# main.net
KiCad netlist of a schematic drawn in Altium Designer
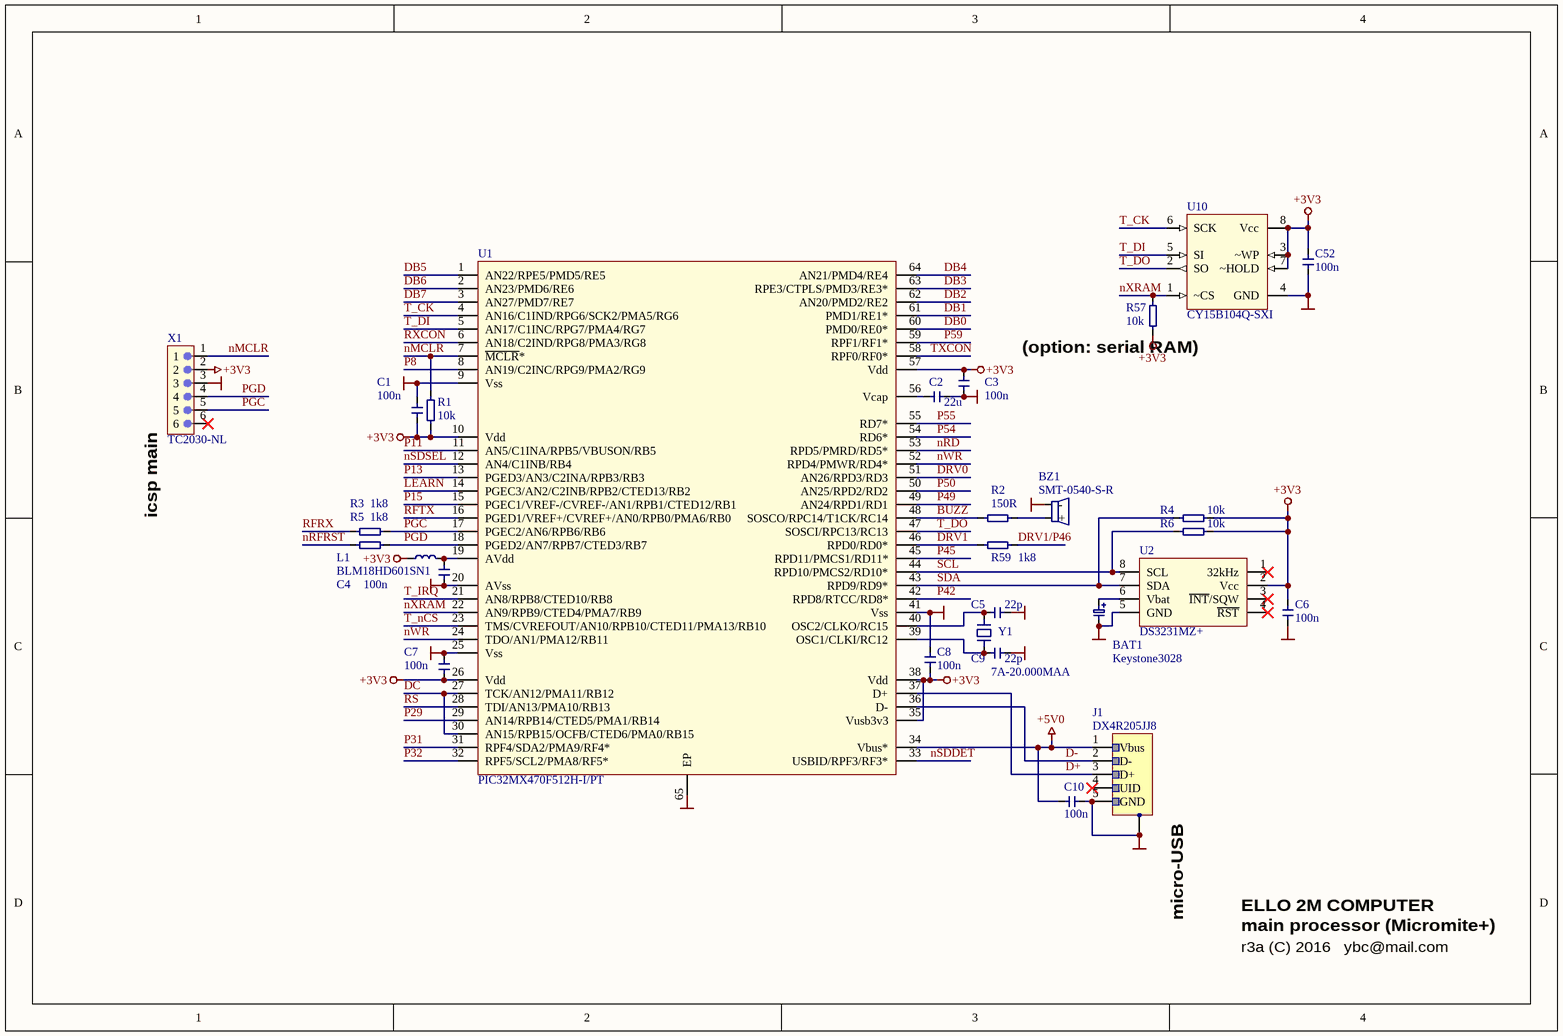
[diagram p0: main.SchDoc]

(export (version "E")
  (design (tool "Eeschema 10.0.6"))
  (components
    (comp (ref "BAT1")
      (value "Keystone3028")
      (footprint "KEYSTONE3028/34")
      (description "Polar capacitor")
      (libsource (lib "Discretes") (part "Capacitor+"))
    )
    (comp (ref "BZ1")
      (value "SMT-0540-S-R")
      (footprint "SMT-0540-S-R")
      (description "Speaker/Buzzer")
      (libsource (lib "Discretes") (part "Speaker"))
    )
    (comp (ref "C1")
      (value "100n")
      (footprint "_0603")
      (description "Capacitor")
      (libsource (lib "Discretes") (part "Capacitor"))
    )
    (comp (ref "C2")
      (value "22u")
      (footprint "_1206")
      (description "Capacitor")
      (libsource (lib "Discretes") (part "Capacitor"))
    )
    (comp (ref "C3")
      (value "100n")
      (footprint "_0603")
      (description "Capacitor")
      (libsource (lib "Discretes") (part "Capacitor"))
    )
    (comp (ref "C4")
      (value "100n")
      (footprint "_0603")
      (description "Capacitor")
      (libsource (lib "Discretes") (part "Capacitor"))
    )
    (comp (ref "C5")
      (value "22p")
      (footprint "_0603")
      (description "Capacitor")
      (libsource (lib "Discretes") (part "Capacitor"))
    )
    (comp (ref "C6")
      (value "100n")
      (footprint "_0603")
      (description "Capacitor")
      (libsource (lib "Discretes") (part "Capacitor"))
    )
    (comp (ref "C7")
      (value "100n")
      (footprint "_0603")
      (description "Capacitor")
      (libsource (lib "Discretes") (part "Capacitor"))
    )
    (comp (ref "C8")
      (value "100n")
      (footprint "_0603")
      (description "Capacitor")
      (libsource (lib "Discretes") (part "Capacitor"))
    )
    (comp (ref "C9")
      (value "22p")
      (footprint "_0603")
      (description "Capacitor")
      (libsource (lib "Discretes") (part "Capacitor"))
    )
    (comp (ref "C10")
      (value "100n")
      (footprint "_0603")
      (description "Capacitor")
      (libsource (lib "Discretes") (part "Capacitor"))
    )
    (comp (ref "C52")
      (value "100n")
      (footprint "_0603")
      (description "Capacitor")
      (libsource (lib "Discretes") (part "Capacitor"))
    )
    (comp (ref "J1")
      (value "DX4R205JJ8")
      (footprint "DX4R205JJ8")
      (description "MicroUSB type A/B, 5 Position SMT Right Angle Receptacle")
      (libsource (lib "Connectors") (part "Mini/Micro USB"))
    )
    (comp (ref "L1")
      (value "BLM18HD601SN1")
      (footprint "_0603")
      (description "Inductor")
      (libsource (lib "Discretes") (part "Inductor"))
    )
    (comp (ref "R1")
      (value "10k")
      (footprint "_0603")
      (description "Resistor")
      (libsource (lib "Discretes") (part "Resistor"))
    )
    (comp (ref "R2")
      (value "150R")
      (footprint "_0603")
      (description "Resistor")
      (libsource (lib "Discretes") (part "Resistor"))
    )
    (comp (ref "R3")
      (value "1k8")
      (footprint "_0603")
      (description "Resistor")
      (libsource (lib "") (part "Resistor_2"))
    )
    (comp (ref "R4")
      (value "10k")
      (footprint "_0603")
      (description "Resistor")
      (libsource (lib "Discretes") (part "Resistor"))
    )
    (comp (ref "R5")
      (value "1k8")
      (footprint "_0603")
      (description "Resistor")
      (libsource (lib "") (part "Resistor_2"))
    )
    (comp (ref "R6")
      (value "10k")
      (footprint "_0603")
      (description "Resistor")
      (libsource (lib "Discretes") (part "Resistor"))
    )
    (comp (ref "R57")
      (value "10k")
      (footprint "_0603")
      (description "Resistor")
      (libsource (lib "") (part "Resistor_2"))
    )
    (comp (ref "R59")
      (value "1k8")
      (footprint "_0603")
      (description "Resistor")
      (libsource (lib "") (part "Resistor_1"))
    )
    (comp (ref "U1")
      (value "PIC32MX470F512H-I/PT")
      (footprint "QFP50P1200X1200X120-65N-S600")
      (fields (field (name "MANUFACTURER") "Microchip"))
      (libsource (lib "IC Microcontrollers and Processors") (part "PIC32MX4xx"))
    )
    (comp (ref "U2")
      (value "DS3231MZ+")
      (footprint "SOIC8")
      (description "I2C Real-Time Clock")
      (fields (field (name "MANUFACTURER") "Maxim Integrated"))
      (libsource (lib "IC Other Functions") (part "DS3231"))
    )
    (comp (ref "U10")
      (value "CY15B104Q-SXI")
      (footprint "SOIC127P790X216-8N")
      (description "Standard 8-pin SPI flash memory")
      (libsource (lib "IC Other Functions") (part "SPI Flash 8pin"))
    )
    (comp (ref "X1")
      (value "TC2030-NL")
      (footprint "TC2030-NL")
      (description "TC2030 nails connector")
      (fields (field (name "MANUFACTURER") "www.tag-connect.com"))
      (libsource (lib "Connectors") (part "TC2030"))
    )
    (comp (ref "Y1")
      (value "7A-20.000MAA")
      (footprint "Crystal 50x32 (2)")
      (description "Crystal Resonator")
      (libsource (lib "Discretes") (part "Crystal"))
    )
  )
  (nets
    (net (code "1") (name "+3V3") (class "Default")
      (node (ref "C1") (pin "2") (pintype "passive"))
      (node (ref "C3") (pin "1") (pintype "passive"))
      (node (ref "C52") (pin "2") (pintype "passive"))
      (node (ref "C6") (pin "1") (pintype "passive"))
      (node (ref "C7") (pin "2") (pintype "passive"))
      (node (ref "C8") (pin "2") (pintype "passive"))
      (node (ref "L1") (pin "1") (pintype "passive"))
      (node (ref "R1") (pin "1") (pintype "passive"))
      (node (ref "R4") (pin "2") (pintype "passive"))
      (node (ref "R57") (pin "1") (pintype "passive"))
      (node (ref "R6") (pin "2") (pintype "passive"))
      (node (ref "U1") (pin "10") (pinfunction "Vdd_10") (pintype "passive"))
      (node (ref "U1") (pin "26") (pinfunction "Vdd_26") (pintype "passive"))
      (node (ref "U1") (pin "35") (pinfunction "Vusb3v3_35") (pintype "passive"))
      (node (ref "U1") (pin "38") (pinfunction "Vdd_38") (pintype "passive"))
      (node (ref "U1") (pin "57") (pinfunction "Vdd_57") (pintype "passive"))
      (node (ref "U10") (pin "3") (pinfunction "~WP_3") (pintype "input"))
      (node (ref "U10") (pin "7") (pinfunction "~HOLD_7") (pintype "input"))
      (node (ref "U10") (pin "8") (pinfunction "Vcc_8") (pintype "power_in"))
      (node (ref "U2") (pin "2") (pinfunction "Vcc_2") (pintype "passive"))
      (node (ref "X1") (pin "2") (pinfunction "2_2") (pintype "passive"))
    )
    (net (code "2") (name "+5V0") (class "Default")
      (node (ref "C10") (pin "2") (pintype "passive"))
      (node (ref "J1") (pin "1") (pinfunction "Vbus_1") (pintype "passive"))
      (node (ref "U1") (pin "34") (pinfunction "Vbus*_34") (pintype "passive"))
    )
    (net (code "3") (name "/BUZZ") (class "Default")
      (node (ref "R2") (pin "1") (pintype "passive"))
      (node (ref "U1") (pin "48") (pinfunction "SOSCO/RPC14/T1CK/RC14_48") (pintype "passive"))
    )
    (net (code "4") (name "/D+") (class "Default")
      (node (ref "J1") (pin "3") (pinfunction "D+_3") (pintype "passive"))
      (node (ref "U1") (pin "37") (pinfunction "D+_37") (pintype "passive"))
    )
    (net (code "5") (name "/D-") (class "Default")
      (node (ref "J1") (pin "2") (pinfunction "D-_2") (pintype "passive"))
      (node (ref "U1") (pin "36") (pinfunction "D-_36") (pintype "passive"))
    )
    (net (code "6") (name "/DB0") (class "Default")
      (node (ref "U1") (pin "60") (pinfunction "PMD0/RE0*_60") (pintype "passive"))
    )
    (net (code "7") (name "/DB1") (class "Default")
      (node (ref "U1") (pin "61") (pinfunction "PMD1/RE1*_61") (pintype "passive"))
    )
    (net (code "8") (name "/DB2") (class "Default")
      (node (ref "U1") (pin "62") (pinfunction "AN20/PMD2/RE2_62") (pintype "passive"))
    )
    (net (code "9") (name "/DB3") (class "Default")
      (node (ref "U1") (pin "63") (pinfunction "RPE3/CTPLS/PMD3/RE3*_63") (pintype "passive"))
    )
    (net (code "10") (name "/DB4") (class "Default")
      (node (ref "U1") (pin "64") (pinfunction "AN21/PMD4/RE4_64") (pintype "passive"))
    )
    (net (code "11") (name "/DB5") (class "Default")
      (node (ref "U1") (pin "1") (pinfunction "AN22/RPE5/PMD5/RE5_1") (pintype "passive"))
    )
    (net (code "12") (name "/DB6") (class "Default")
      (node (ref "U1") (pin "2") (pinfunction "AN23/PMD6/RE6_2") (pintype "passive"))
    )
    (net (code "13") (name "/DB7") (class "Default")
      (node (ref "U1") (pin "3") (pinfunction "AN27/PMD7/RE7_3") (pintype "passive"))
    )
    (net (code "14") (name "/DC") (class "Default")
      (node (ref "U1") (pin "27") (pinfunction "TCK/AN12/PMA11/RB12_27") (pintype "passive"))
      (node (ref "U1") (pin "30") (pinfunction "AN15/RPB15/OCFB/CTED6/PMA0/RB15_30") (pintype "passive"))
    )
    (net (code "15") (name "/DRV0") (class "Default")
      (node (ref "U1") (pin "51") (pinfunction "AN26/RPD3/RD3_51") (pintype "passive"))
    )
    (net (code "16") (name "/DRV1") (class "Default")
      (node (ref "R59") (pin "2") (pintype "passive"))
      (node (ref "U1") (pin "46") (pinfunction "RPD0/RD0*_46") (pintype "passive"))
    )
    (net (code "17") (name "/DRV1{slash}P46") (class "Default")
      (node (ref "R59") (pin "1") (pintype "passive"))
    )
    (net (code "18") (name "/LEARN") (class "Default")
      (node (ref "U1") (pin "14") (pinfunction "PGEC3/AN2/C2INB/RPB2/CTED13/RB2_14") (pintype "passive"))
    )
    (net (code "19") (name "/P8") (class "Default")
      (node (ref "U1") (pin "8") (pinfunction "AN19/C2INC/RPG9/PMA2/RG9_8") (pintype "passive"))
    )
    (net (code "20") (name "/P11") (class "Default")
      (node (ref "U1") (pin "11") (pinfunction "AN5/C1INA/RPB5/VBUSON/RB5_11") (pintype "passive"))
    )
    (net (code "21") (name "/P13") (class "Default")
      (node (ref "U1") (pin "13") (pinfunction "PGED3/AN3/C2INA/RPB3/RB3_13") (pintype "passive"))
    )
    (net (code "22") (name "/P15") (class "Default")
      (node (ref "U1") (pin "15") (pinfunction "PGEC1/VREF-/CVREF-/AN1/RPB1/CTED12/RB1_15") (pintype "passive"))
    )
    (net (code "23") (name "/P29") (class "Default")
      (node (ref "U1") (pin "29") (pinfunction "AN14/RPB14/CTED5/PMA1/RB14_29") (pintype "passive"))
    )
    (net (code "24") (name "/P31") (class "Default")
      (node (ref "U1") (pin "31") (pinfunction "RPF4/SDA2/PMA9/RF4*_31") (pintype "passive"))
    )
    (net (code "25") (name "/P32") (class "Default")
      (node (ref "U1") (pin "32") (pinfunction "RPF5/SCL2/PMA8/RF5*_32") (pintype "passive"))
    )
    (net (code "26") (name "/P42") (class "Default")
      (node (ref "U1") (pin "42") (pinfunction "RPD8/RTCC/RD8*_42") (pintype "passive"))
    )
    (net (code "27") (name "/P45") (class "Default")
      (node (ref "U1") (pin "45") (pinfunction "RPD11/PMCS1/RD11*_45") (pintype "passive"))
    )
    (net (code "28") (name "/P49") (class "Default")
      (node (ref "U1") (pin "49") (pinfunction "AN24/RPD1/RD1_49") (pintype "passive"))
    )
    (net (code "29") (name "/P50") (class "Default")
      (node (ref "U1") (pin "50") (pinfunction "AN25/RPD2/RD2_50") (pintype "passive"))
    )
    (net (code "30") (name "/P54") (class "Default")
      (node (ref "U1") (pin "54") (pinfunction "RD6*_54") (pintype "passive"))
    )
    (net (code "31") (name "/P55") (class "Default")
      (node (ref "U1") (pin "55") (pinfunction "RD7*_55") (pintype "passive"))
    )
    (net (code "32") (name "/P59") (class "Default")
      (node (ref "U1") (pin "59") (pinfunction "RPF1/RF1*_59") (pintype "passive"))
    )
    (net (code "33") (name "/PGC") (class "Default")
      (node (ref "R3") (pin "2") (pintype "passive"))
      (node (ref "U1") (pin "17") (pinfunction "PGEC2/AN6/RPB6/RB6_17") (pintype "passive"))
      (node (ref "X1") (pin "5") (pinfunction "5_5") (pintype "passive"))
    )
    (net (code "34") (name "/PGD") (class "Default")
      (node (ref "R5") (pin "2") (pintype "passive"))
      (node (ref "U1") (pin "18") (pinfunction "PGED2/AN7/RPB7/CTED3/RB7_18") (pintype "passive"))
      (node (ref "X1") (pin "4") (pinfunction "4_4") (pintype "passive"))
    )
    (net (code "35") (name "/RFRX") (class "Default") (node (ref "R3") (pin "1") (pintype "passive")))
    (net (code "36") (name "/RFTX") (class "Default")
      (node (ref "U1") (pin "16") (pinfunction "PGED1/VREF+/CVREF+/AN0/RPB0/PMA6/RB0_16") (pintype "passive"))
    )
    (net (code "37") (name "/RS") (class "Default")
      (node (ref "U1") (pin "28") (pinfunction "TDI/AN13/PMA10/RB13_28") (pintype "passive"))
    )
    (net (code "38") (name "/RXCON") (class "Default")
      (node (ref "U1") (pin "6") (pinfunction "AN18/C2IND/RPG8/PMA3/RG8_6") (pintype "passive"))
    )
    (net (code "39") (name "/SCL") (class "Default")
      (node (ref "R6") (pin "1") (pintype "passive"))
      (node (ref "U1") (pin "44") (pinfunction "RPD10/PMCS2/RD10*_44") (pintype "passive"))
      (node (ref "U2") (pin "8") (pinfunction "SCL_8") (pintype "passive"))
    )
    (net (code "40") (name "/SDA") (class "Default")
      (node (ref "R4") (pin "1") (pintype "passive"))
      (node (ref "U1") (pin "43") (pinfunction "RPD9/RD9*_43") (pintype "passive"))
      (node (ref "U2") (pin "7") (pinfunction "SDA_7") (pintype "passive"))
    )
    (net (code "41") (name "/TXCON") (class "Default")
      (node (ref "U1") (pin "58") (pinfunction "RPF0/RF0*_58") (pintype "passive"))
    )
    (net (code "42") (name "/T_CK") (class "Default")
      (node (ref "U1") (pin "4") (pinfunction "AN16/C1IND/RPG6/SCK2/PMA5/RG6_4") (pintype "passive"))
      (node (ref "U10") (pin "6") (pinfunction "SCK_6") (pintype "input"))
    )
    (net (code "43") (name "/T_DI") (class "Default")
      (node (ref "U1") (pin "5") (pinfunction "AN17/C1INC/RPG7/PMA4/RG7_5") (pintype "passive"))
      (node (ref "U10") (pin "5") (pinfunction "SI_5") (pintype "input"))
    )
    (net (code "44") (name "/T_DO") (class "Default")
      (node (ref "U1") (pin "47") (pinfunction "SOSCI/RPC13/RC13_47") (pintype "passive"))
      (node (ref "U10") (pin "2") (pinfunction "SO_2") (pintype "output"))
    )
    (net (code "45") (name "/T_IRQ") (class "Default")
      (node (ref "U1") (pin "21") (pinfunction "AN8/RPB8/CTED10/RB8_21") (pintype "passive"))
    )
    (net (code "46") (name "/T_nCS") (class "Default")
      (node (ref "U1") (pin "23") (pinfunction "TMS/CVREFOUT/AN10/RPB10/CTED11/PMA13/RB10_23") (pintype "passive"))
    )
    (net (code "47") (name "/nMCLR") (class "Default")
      (node (ref "R1") (pin "2") (pintype "passive"))
      (node (ref "U1") (pin "7") (pinfunction "~{MCLR}*_7") (pintype "passive"))
      (node (ref "X1") (pin "1") (pinfunction "1_1") (pintype "passive"))
    )
    (net (code "48") (name "/nRD") (class "Default")
      (node (ref "U1") (pin "53") (pinfunction "RPD5/PMRD/RD5*_53") (pintype "passive"))
    )
    (net (code "49") (name "/nRFRST") (class "Default") (node (ref "R5") (pin "1") (pintype "passive")))
    (net (code "50") (name "/nSDDET") (class "Default")
      (node (ref "U1") (pin "33") (pinfunction "USBID/RPF3/RF3*_33") (pintype "passive"))
    )
    (net (code "51") (name "/nSDSEL") (class "Default")
      (node (ref "U1") (pin "12") (pinfunction "AN4/C1INB/RB4_12") (pintype "passive"))
    )
    (net (code "52") (name "/nWR") (class "Default")
      (node (ref "U1") (pin "24") (pinfunction "TDO/AN1/PMA12/RB11_24") (pintype "passive"))
      (node (ref "U1") (pin "52") (pinfunction "RPD4/PMWR/RD4*_52") (pintype "passive"))
    )
    (net (code "53") (name "/nXRAM") (class "Default")
      (node (ref "R57") (pin "2") (pintype "passive"))
      (node (ref "U1") (pin "22") (pinfunction "AN9/RPB9/CTED4/PMA7/RB9_22") (pintype "passive"))
      (node (ref "U10") (pin "1") (pinfunction "~CS_1") (pintype "input"))
    )
    (net (code "54") (name "GND") (class "Default")
      (node (ref "BAT1") (pin "-") (pintype "passive"))
      (node (ref "BZ1") (pin "2") (pinfunction "-_2") (pintype "passive"))
      (node (ref "C1") (pin "1") (pintype "passive"))
      (node (ref "C10") (pin "1") (pintype "passive"))
      (node (ref "C2") (pin "1") (pintype "passive"))
      (node (ref "C3") (pin "2") (pintype "passive"))
      (node (ref "C4") (pin "2") (pintype "passive"))
      (node (ref "C5") (pin "2") (pintype "passive"))
      (node (ref "C52") (pin "1") (pintype "passive"))
      (node (ref "C6") (pin "2") (pintype "passive"))
      (node (ref "C7") (pin "1") (pintype "passive"))
      (node (ref "C8") (pin "1") (pintype "passive"))
      (node (ref "C9") (pin "2") (pintype "passive"))
      (node (ref "J1") (pin "5") (pinfunction "SH_5") (pintype "passive"))
      (node (ref "U1") (pin "20") (pinfunction "AVss_20") (pintype "passive"))
      (node (ref "U1") (pin "25") (pinfunction "Vss_25") (pintype "passive"))
      (node (ref "U1") (pin "41") (pinfunction "Vss_41") (pintype "passive"))
      (node (ref "U1") (pin "65") (pinfunction "EP_65") (pintype "passive"))
      (node (ref "U1") (pin "9") (pinfunction "Vss_9") (pintype "passive"))
      (node (ref "U10") (pin "4") (pinfunction "GND_4") (pintype "power_in"))
      (node (ref "U2") (pin "5") (pinfunction "GND_5") (pintype "passive"))
      (node (ref "X1") (pin "3") (pinfunction "3_3") (pintype "passive"))
    )
    (net (code "55") (name "Net-(BZ1-+)") (class "Default")
      (node (ref "BZ1") (pin "1") (pinfunction "+_1") (pintype "passive"))
      (node (ref "R2") (pin "2") (pintype "passive"))
    )
    (net (code "56") (name "Net-(U1-AVdd)") (class "Default")
      (node (ref "C4") (pin "1") (pintype "passive"))
      (node (ref "L1") (pin "2") (pintype "passive"))
      (node (ref "U1") (pin "19") (pinfunction "AVdd_19") (pintype "passive"))
    )
    (net (code "57") (name "Net-(U1-OSC1{slash}CLKI{slash}RC12)") (class "Default")
      (node (ref "C9") (pin "1") (pintype "passive"))
      (node (ref "U1") (pin "39") (pinfunction "OSC1/CLKI/RC12_39") (pintype "passive"))
      (node (ref "Y1") (pin "1") (pintype "passive"))
    )
    (net (code "58") (name "Net-(U1-OSC2{slash}CLKO{slash}RC15)") (class "Default")
      (node (ref "C5") (pin "1") (pintype "passive"))
      (node (ref "U1") (pin "40") (pinfunction "OSC2/CLKO/RC15_40") (pintype "passive"))
      (node (ref "Y1") (pin "2") (pintype "passive"))
    )
    (net (code "59") (name "Net-(U1-Vcap)") (class "Default")
      (node (ref "C2") (pin "2") (pintype "passive"))
      (node (ref "U1") (pin "56") (pinfunction "Vcap_56") (pintype "passive"))
    )
    (net (code "60") (name "Net-(U2-Vbat)") (class "Default")
      (node (ref "BAT1") (pin "+") (pintype "passive"))
      (node (ref "U2") (pin "6") (pinfunction "Vbat_6") (pintype "passive"))
    )
    (net (code "61") (name "unconnected-(J1-UID-Pad4)") (class "Default")
      (node (ref "J1") (pin "4") (pinfunction "UID_4") (pintype "passive+no_connect"))
    )
    (net (code "62") (name "unconnected-(U2-32kHz-Pad1)") (class "Default")
      (node (ref "U2") (pin "1") (pinfunction "32kHz_1") (pintype "passive+no_connect"))
    )
    (net (code "63") (name "unconnected-(U2-~{INT}{slash}SQW-Pad3)") (class "Default")
      (node (ref "U2") (pin "3") (pinfunction "~{INT}/SQW_3") (pintype "passive+no_connect"))
    )
    (net (code "64") (name "unconnected-(U2-~{RST}-Pad4)") (class "Default")
      (node (ref "U2") (pin "4") (pinfunction "~{RST}_4") (pintype "passive+no_connect"))
    )
    (net (code "65") (name "unconnected-(X1-Pad6)") (class "Default")
      (node (ref "X1") (pin "6") (pinfunction "6_6") (pintype "passive+no_connect"))
    )
  )
)
